# FPGA2_POWER.net
KiCad netlist of a schematic drawn in Altium Designer
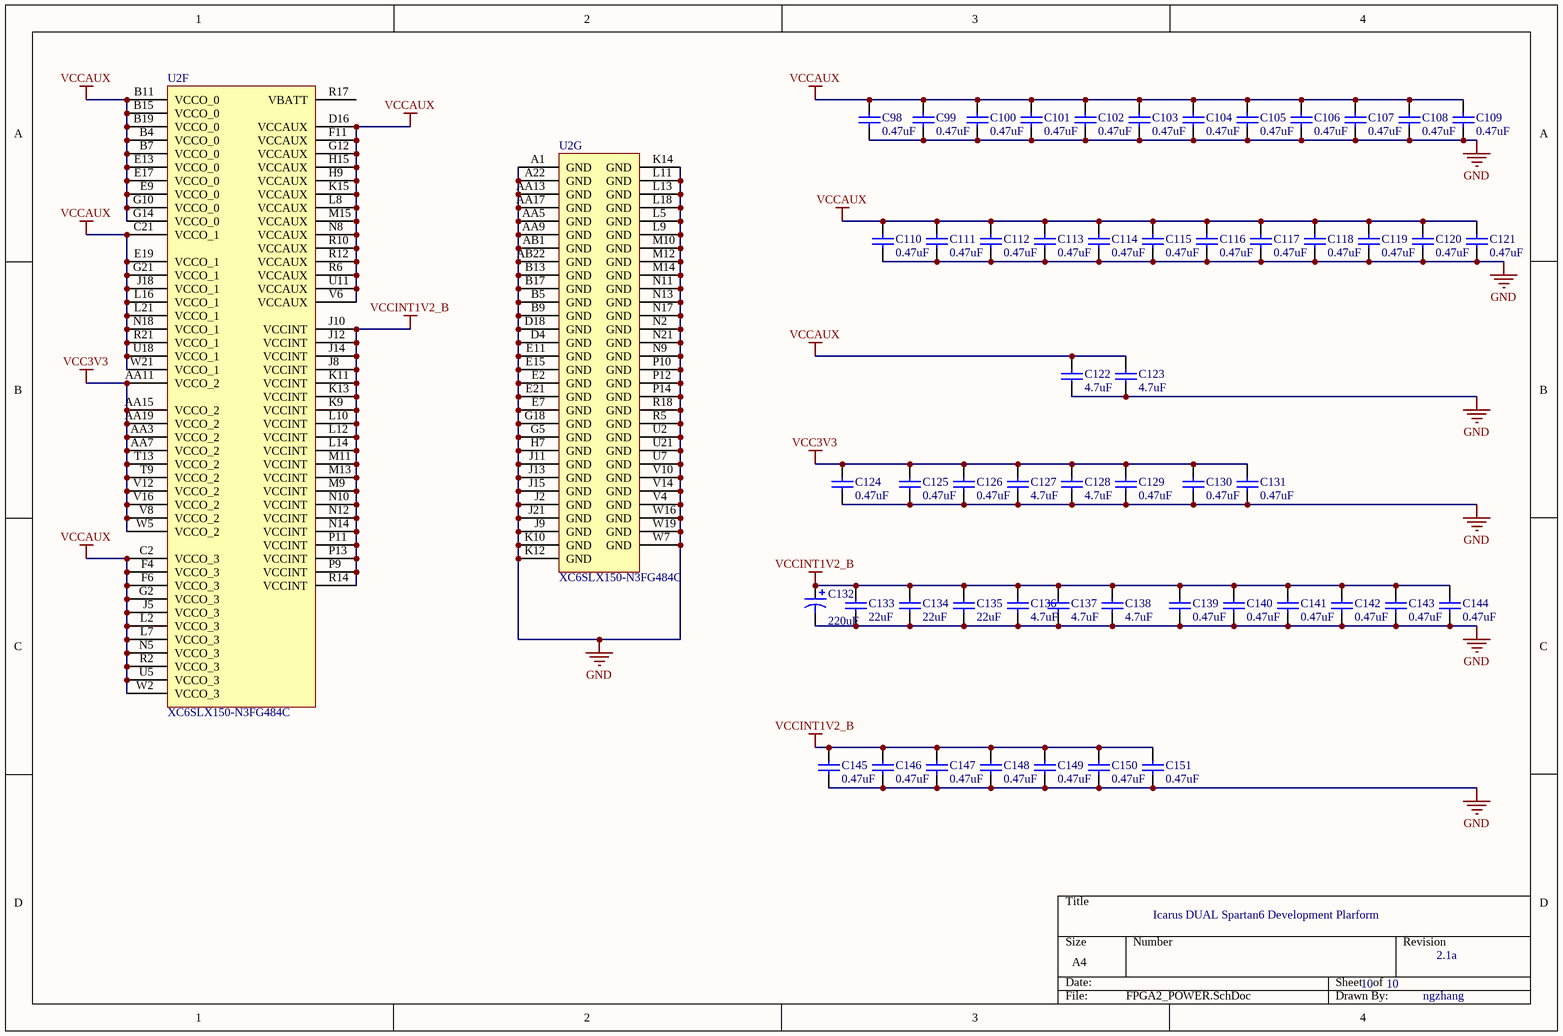
[diagram p0: FPGA2_POWER.SchDoc]

(export (version "E")
  (design (tool "Eeschema 10.0.6"))
  (components
    (comp (ref "C98")
      (value "0.47uF")
      (footprint "0402")
      (description "Capacitor (Semiconductor SIM Model)")
      (fields (field (name "PUBLISHER") "Altium Limited"))
      (libsource (lib "Miscellaneous Devices") (part "Cap Semi"))
    )
    (comp (ref "C99")
      (value "0.47uF")
      (footprint "0402")
      (description "Capacitor (Semiconductor SIM Model)")
      (fields (field (name "PUBLISHER") "Altium Limited"))
      (libsource (lib "Miscellaneous Devices") (part "Cap Semi"))
    )
    (comp (ref "C100")
      (value "0.47uF")
      (footprint "0402")
      (description "Capacitor (Semiconductor SIM Model)")
      (fields (field (name "PUBLISHER") "Altium Limited"))
      (libsource (lib "Miscellaneous Devices") (part "Cap Semi"))
    )
    (comp (ref "C101")
      (value "0.47uF")
      (footprint "0402")
      (description "Capacitor (Semiconductor SIM Model)")
      (fields (field (name "PUBLISHER") "Altium Limited"))
      (libsource (lib "Miscellaneous Devices") (part "Cap Semi"))
    )
    (comp (ref "C102")
      (value "0.47uF")
      (footprint "0402")
      (description "Capacitor (Semiconductor SIM Model)")
      (fields (field (name "PUBLISHER") "Altium Limited"))
      (libsource (lib "Miscellaneous Devices") (part "Cap Semi"))
    )
    (comp (ref "C103")
      (value "0.47uF")
      (footprint "0402")
      (description "Capacitor (Semiconductor SIM Model)")
      (fields (field (name "PUBLISHER") "Altium Limited"))
      (libsource (lib "Miscellaneous Devices") (part "Cap Semi"))
    )
    (comp (ref "C104")
      (value "0.47uF")
      (footprint "0402")
      (description "Capacitor (Semiconductor SIM Model)")
      (fields (field (name "PUBLISHER") "Altium Limited"))
      (libsource (lib "Miscellaneous Devices") (part "Cap Semi"))
    )
    (comp (ref "C105")
      (value "0.47uF")
      (footprint "0402")
      (description "Capacitor (Semiconductor SIM Model)")
      (fields (field (name "PUBLISHER") "Altium Limited"))
      (libsource (lib "Miscellaneous Devices") (part "Cap Semi"))
    )
    (comp (ref "C106")
      (value "0.47uF")
      (footprint "0402")
      (description "Capacitor (Semiconductor SIM Model)")
      (fields (field (name "PUBLISHER") "Altium Limited"))
      (libsource (lib "Miscellaneous Devices") (part "Cap Semi"))
    )
    (comp (ref "C107")
      (value "0.47uF")
      (footprint "0402")
      (description "Capacitor (Semiconductor SIM Model)")
      (fields (field (name "PUBLISHER") "Altium Limited"))
      (libsource (lib "Miscellaneous Devices") (part "Cap Semi"))
    )
    (comp (ref "C108")
      (value "0.47uF")
      (footprint "0402")
      (description "Capacitor (Semiconductor SIM Model)")
      (fields (field (name "PUBLISHER") "Altium Limited"))
      (libsource (lib "Miscellaneous Devices") (part "Cap Semi"))
    )
    (comp (ref "C109")
      (value "0.47uF")
      (footprint "0402")
      (description "Capacitor (Semiconductor SIM Model)")
      (fields (field (name "PUBLISHER") "Altium Limited"))
      (libsource (lib "Miscellaneous Devices") (part "Cap Semi"))
    )
    (comp (ref "C110")
      (value "0.47uF")
      (footprint "0402")
      (description "Capacitor (Semiconductor SIM Model)")
      (fields (field (name "PUBLISHER") "Altium Limited"))
      (libsource (lib "Miscellaneous Devices") (part "Cap Semi"))
    )
    (comp (ref "C111")
      (value "0.47uF")
      (footprint "0402")
      (description "Capacitor (Semiconductor SIM Model)")
      (fields (field (name "PUBLISHER") "Altium Limited"))
      (libsource (lib "Miscellaneous Devices") (part "Cap Semi"))
    )
    (comp (ref "C112")
      (value "0.47uF")
      (footprint "0402")
      (description "Capacitor (Semiconductor SIM Model)")
      (fields (field (name "PUBLISHER") "Altium Limited"))
      (libsource (lib "Miscellaneous Devices") (part "Cap Semi"))
    )
    (comp (ref "C113")
      (value "0.47uF")
      (footprint "0402")
      (description "Capacitor (Semiconductor SIM Model)")
      (fields (field (name "PUBLISHER") "Altium Limited"))
      (libsource (lib "Miscellaneous Devices") (part "Cap Semi"))
    )
    (comp (ref "C114")
      (value "0.47uF")
      (footprint "0402")
      (description "Capacitor (Semiconductor SIM Model)")
      (fields (field (name "PUBLISHER") "Altium Limited"))
      (libsource (lib "Miscellaneous Devices") (part "Cap Semi"))
    )
    (comp (ref "C115")
      (value "0.47uF")
      (footprint "0402")
      (description "Capacitor (Semiconductor SIM Model)")
      (fields (field (name "PUBLISHER") "Altium Limited"))
      (libsource (lib "Miscellaneous Devices") (part "Cap Semi"))
    )
    (comp (ref "C116")
      (value "0.47uF")
      (footprint "0402")
      (description "Capacitor (Semiconductor SIM Model)")
      (fields (field (name "PUBLISHER") "Altium Limited"))
      (libsource (lib "Miscellaneous Devices") (part "Cap Semi"))
    )
    (comp (ref "C117")
      (value "0.47uF")
      (footprint "0402")
      (description "Capacitor (Semiconductor SIM Model)")
      (fields (field (name "PUBLISHER") "Altium Limited"))
      (libsource (lib "Miscellaneous Devices") (part "Cap Semi"))
    )
    (comp (ref "C118")
      (value "0.47uF")
      (footprint "0402")
      (description "Capacitor (Semiconductor SIM Model)")
      (fields (field (name "PUBLISHER") "Altium Limited"))
      (libsource (lib "Miscellaneous Devices") (part "Cap Semi"))
    )
    (comp (ref "C119")
      (value "0.47uF")
      (footprint "0402")
      (description "Capacitor (Semiconductor SIM Model)")
      (fields (field (name "PUBLISHER") "Altium Limited"))
      (libsource (lib "Miscellaneous Devices") (part "Cap Semi"))
    )
    (comp (ref "C120")
      (value "0.47uF")
      (footprint "0402")
      (description "Capacitor (Semiconductor SIM Model)")
      (fields (field (name "PUBLISHER") "Altium Limited"))
      (libsource (lib "Miscellaneous Devices") (part "Cap Semi"))
    )
    (comp (ref "C121")
      (value "0.47uF")
      (footprint "0402")
      (description "Capacitor (Semiconductor SIM Model)")
      (fields (field (name "PUBLISHER") "Altium Limited"))
      (libsource (lib "Miscellaneous Devices") (part "Cap Semi"))
    )
    (comp (ref "C122")
      (value "4.7uF")
      (footprint "C0805")
      (description "Capacitor (Semiconductor SIM Model)")
      (fields (field (name "PUBLISHER") "Altium Limited"))
      (libsource (lib "Miscellaneous Devices") (part "Cap Semi"))
    )
    (comp (ref "C123")
      (value "4.7uF")
      (footprint "C0805")
      (description "Capacitor (Semiconductor SIM Model)")
      (fields (field (name "PUBLISHER") "Altium Limited"))
      (libsource (lib "Miscellaneous Devices") (part "Cap Semi"))
    )
    (comp (ref "C124")
      (value "0.47uF")
      (footprint "0402")
      (description "Capacitor (Semiconductor SIM Model)")
      (fields (field (name "PUBLISHER") "Altium Limited"))
      (libsource (lib "Miscellaneous Devices") (part "Cap Semi"))
    )
    (comp (ref "C125")
      (value "0.47uF")
      (footprint "0402")
      (description "Capacitor (Semiconductor SIM Model)")
      (fields (field (name "PUBLISHER") "Altium Limited"))
      (libsource (lib "Miscellaneous Devices") (part "Cap Semi"))
    )
    (comp (ref "C126")
      (value "0.47uF")
      (footprint "0402")
      (description "Capacitor (Semiconductor SIM Model)")
      (fields (field (name "PUBLISHER") "Altium Limited"))
      (libsource (lib "Miscellaneous Devices") (part "Cap Semi"))
    )
    (comp (ref "C127")
      (value "4.7uF")
      (footprint "C0805")
      (description "Capacitor (Semiconductor SIM Model)")
      (fields (field (name "PUBLISHER") "Altium Limited"))
      (libsource (lib "Miscellaneous Devices") (part "Cap Semi"))
    )
    (comp (ref "C128")
      (value "4.7uF")
      (footprint "C0805")
      (description "Capacitor (Semiconductor SIM Model)")
      (fields (field (name "PUBLISHER") "Altium Limited"))
      (libsource (lib "Miscellaneous Devices") (part "Cap Semi"))
    )
    (comp (ref "C129")
      (value "0.47uF")
      (footprint "0402")
      (description "Capacitor (Semiconductor SIM Model)")
      (fields (field (name "PUBLISHER") "Altium Limited"))
      (libsource (lib "Miscellaneous Devices") (part "Cap Semi"))
    )
    (comp (ref "C130")
      (value "0.47uF")
      (footprint "0402")
      (description "Capacitor (Semiconductor SIM Model)")
      (fields (field (name "PUBLISHER") "Altium Limited"))
      (libsource (lib "Miscellaneous Devices") (part "Cap Semi"))
    )
    (comp (ref "C131")
      (value "0.47uF")
      (footprint "0402")
      (description "Capacitor (Semiconductor SIM Model)")
      (fields (field (name "PUBLISHER") "Altium Limited"))
      (libsource (lib "Miscellaneous Devices") (part "Cap Semi"))
    )
    (comp (ref "C132")
      (value "220uF")
      (footprint "D")
      (description "Polarized Capacitor (Surface Mount)")
      (fields (field (name "PUBLISHER") "Altium Limited"))
      (libsource (lib "Miscellaneous Devices") (part "Cap Pol3"))
    )
    (comp (ref "C133")
      (value "22uF")
      (footprint "C1206")
      (description "Capacitor (Semiconductor SIM Model)")
      (fields (field (name "PUBLISHER") "Altium Limited"))
      (libsource (lib "Miscellaneous Devices") (part "Cap Semi"))
    )
    (comp (ref "C134")
      (value "22uF")
      (footprint "C1206")
      (description "Capacitor (Semiconductor SIM Model)")
      (fields (field (name "PUBLISHER") "Altium Limited"))
      (libsource (lib "Miscellaneous Devices") (part "Cap Semi"))
    )
    (comp (ref "C135")
      (value "22uF")
      (footprint "C1206")
      (description "Capacitor (Semiconductor SIM Model)")
      (fields (field (name "PUBLISHER") "Altium Limited"))
      (libsource (lib "Miscellaneous Devices") (part "Cap Semi"))
    )
    (comp (ref "C136")
      (value "4.7uF")
      (footprint "C0805")
      (description "Capacitor (Semiconductor SIM Model)")
      (fields (field (name "PUBLISHER") "Altium Limited"))
      (libsource (lib "Miscellaneous Devices") (part "Cap Semi"))
    )
    (comp (ref "C137")
      (value "4.7uF")
      (footprint "C0805")
      (description "Capacitor (Semiconductor SIM Model)")
      (fields (field (name "PUBLISHER") "Altium Limited"))
      (libsource (lib "Miscellaneous Devices") (part "Cap Semi"))
    )
    (comp (ref "C138")
      (value "4.7uF")
      (footprint "C0805")
      (description "Capacitor (Semiconductor SIM Model)")
      (fields (field (name "PUBLISHER") "Altium Limited"))
      (libsource (lib "Miscellaneous Devices") (part "Cap Semi"))
    )
    (comp (ref "C139")
      (value "0.47uF")
      (footprint "0402")
      (description "Capacitor (Semiconductor SIM Model)")
      (fields (field (name "PUBLISHER") "Altium Limited"))
      (libsource (lib "Miscellaneous Devices") (part "Cap Semi"))
    )
    (comp (ref "C140")
      (value "0.47uF")
      (footprint "0402")
      (description "Capacitor (Semiconductor SIM Model)")
      (fields (field (name "PUBLISHER") "Altium Limited"))
      (libsource (lib "Miscellaneous Devices") (part "Cap Semi"))
    )
    (comp (ref "C141")
      (value "0.47uF")
      (footprint "0402")
      (description "Capacitor (Semiconductor SIM Model)")
      (fields (field (name "PUBLISHER") "Altium Limited"))
      (libsource (lib "Miscellaneous Devices") (part "Cap Semi"))
    )
    (comp (ref "C142")
      (value "0.47uF")
      (footprint "0402")
      (description "Capacitor (Semiconductor SIM Model)")
      (fields (field (name "PUBLISHER") "Altium Limited"))
      (libsource (lib "Miscellaneous Devices") (part "Cap Semi"))
    )
    (comp (ref "C143")
      (value "0.47uF")
      (footprint "0402")
      (description "Capacitor (Semiconductor SIM Model)")
      (fields (field (name "PUBLISHER") "Altium Limited"))
      (libsource (lib "Miscellaneous Devices") (part "Cap Semi"))
    )
    (comp (ref "C144")
      (value "0.47uF")
      (footprint "0402")
      (description "Capacitor (Semiconductor SIM Model)")
      (fields (field (name "PUBLISHER") "Altium Limited"))
      (libsource (lib "Miscellaneous Devices") (part "Cap Semi"))
    )
    (comp (ref "C145")
      (value "0.47uF")
      (footprint "0402")
      (description "Capacitor (Semiconductor SIM Model)")
      (fields (field (name "PUBLISHER") "Altium Limited"))
      (libsource (lib "Miscellaneous Devices") (part "Cap Semi"))
    )
    (comp (ref "C146")
      (value "0.47uF")
      (footprint "0402")
      (description "Capacitor (Semiconductor SIM Model)")
      (fields (field (name "PUBLISHER") "Altium Limited"))
      (libsource (lib "Miscellaneous Devices") (part "Cap Semi"))
    )
    (comp (ref "C147")
      (value "0.47uF")
      (footprint "0402")
      (description "Capacitor (Semiconductor SIM Model)")
      (fields (field (name "PUBLISHER") "Altium Limited"))
      (libsource (lib "Miscellaneous Devices") (part "Cap Semi"))
    )
    (comp (ref "C148")
      (value "0.47uF")
      (footprint "0402")
      (description "Capacitor (Semiconductor SIM Model)")
      (fields (field (name "PUBLISHER") "Altium Limited"))
      (libsource (lib "Miscellaneous Devices") (part "Cap Semi"))
    )
    (comp (ref "C149")
      (value "0.47uF")
      (footprint "0402")
      (description "Capacitor (Semiconductor SIM Model)")
      (fields (field (name "PUBLISHER") "Altium Limited"))
      (libsource (lib "Miscellaneous Devices") (part "Cap Semi"))
    )
    (comp (ref "C150")
      (value "0.47uF")
      (footprint "0402")
      (description "Capacitor (Semiconductor SIM Model)")
      (fields (field (name "PUBLISHER") "Altium Limited"))
      (libsource (lib "Miscellaneous Devices") (part "Cap Semi"))
    )
    (comp (ref "C151")
      (value "0.47uF")
      (footprint "0402")
      (description "Capacitor (Semiconductor SIM Model)")
      (fields (field (name "PUBLISHER") "Altium Limited"))
      (libsource (lib "Miscellaneous Devices") (part "Cap Semi"))
    )
    (comp (ref "U2")
      (value "XC6SLX150-N3FG484C")
      (footprint "FG484")
      (fields (field (name "PUBLISHER") "Altium Limited"))
      (libsource (lib "Xilinx Spartan-6") (part "XC6SLX150-N3FG484C"))
    )
  )
  (nets
    (net (code "1") (name "GND") (class "Default")
      (node (ref "C100") (pin "1") (pinfunction "1_1") (pintype "passive"))
      (node (ref "C101") (pin "1") (pinfunction "1_1") (pintype "passive"))
      (node (ref "C102") (pin "1") (pinfunction "1_1") (pintype "passive"))
      (node (ref "C103") (pin "1") (pinfunction "1_1") (pintype "passive"))
      (node (ref "C104") (pin "1") (pinfunction "1_1") (pintype "passive"))
      (node (ref "C105") (pin "1") (pinfunction "1_1") (pintype "passive"))
      (node (ref "C106") (pin "1") (pinfunction "1_1") (pintype "passive"))
      (node (ref "C107") (pin "1") (pinfunction "1_1") (pintype "passive"))
      (node (ref "C108") (pin "1") (pinfunction "1_1") (pintype "passive"))
      (node (ref "C109") (pin "1") (pinfunction "1_1") (pintype "passive"))
      (node (ref "C110") (pin "1") (pinfunction "1_1") (pintype "passive"))
      (node (ref "C111") (pin "1") (pinfunction "1_1") (pintype "passive"))
      (node (ref "C112") (pin "1") (pinfunction "1_1") (pintype "passive"))
      (node (ref "C113") (pin "1") (pinfunction "1_1") (pintype "passive"))
      (node (ref "C114") (pin "1") (pinfunction "1_1") (pintype "passive"))
      (node (ref "C115") (pin "1") (pinfunction "1_1") (pintype "passive"))
      (node (ref "C116") (pin "1") (pinfunction "1_1") (pintype "passive"))
      (node (ref "C117") (pin "1") (pinfunction "1_1") (pintype "passive"))
      (node (ref "C118") (pin "1") (pinfunction "1_1") (pintype "passive"))
      (node (ref "C119") (pin "1") (pinfunction "1_1") (pintype "passive"))
      (node (ref "C120") (pin "1") (pinfunction "1_1") (pintype "passive"))
      (node (ref "C121") (pin "1") (pinfunction "1_1") (pintype "passive"))
      (node (ref "C122") (pin "1") (pinfunction "1_1") (pintype "passive"))
      (node (ref "C123") (pin "1") (pinfunction "1_1") (pintype "passive"))
      (node (ref "C124") (pin "1") (pinfunction "1_1") (pintype "passive"))
      (node (ref "C125") (pin "1") (pinfunction "1_1") (pintype "passive"))
      (node (ref "C126") (pin "1") (pinfunction "1_1") (pintype "passive"))
      (node (ref "C127") (pin "1") (pinfunction "1_1") (pintype "passive"))
      (node (ref "C128") (pin "1") (pinfunction "1_1") (pintype "passive"))
      (node (ref "C129") (pin "1") (pinfunction "1_1") (pintype "passive"))
      (node (ref "C130") (pin "1") (pinfunction "1_1") (pintype "passive"))
      (node (ref "C131") (pin "1") (pinfunction "1_1") (pintype "passive"))
      (node (ref "C132") (pin "2") (pinfunction "2_2") (pintype "passive"))
      (node (ref "C133") (pin "1") (pinfunction "1_1") (pintype "passive"))
      (node (ref "C134") (pin "1") (pinfunction "1_1") (pintype "passive"))
      (node (ref "C135") (pin "1") (pinfunction "1_1") (pintype "passive"))
      (node (ref "C136") (pin "1") (pinfunction "1_1") (pintype "passive"))
      (node (ref "C137") (pin "1") (pinfunction "1_1") (pintype "passive"))
      (node (ref "C138") (pin "1") (pinfunction "1_1") (pintype "passive"))
      (node (ref "C139") (pin "1") (pinfunction "1_1") (pintype "passive"))
      (node (ref "C140") (pin "1") (pinfunction "1_1") (pintype "passive"))
      (node (ref "C141") (pin "1") (pinfunction "1_1") (pintype "passive"))
      (node (ref "C142") (pin "1") (pinfunction "1_1") (pintype "passive"))
      (node (ref "C143") (pin "1") (pinfunction "1_1") (pintype "passive"))
      (node (ref "C144") (pin "1") (pinfunction "1_1") (pintype "passive"))
      (node (ref "C145") (pin "1") (pinfunction "1_1") (pintype "passive"))
      (node (ref "C146") (pin "1") (pinfunction "1_1") (pintype "passive"))
      (node (ref "C147") (pin "1") (pinfunction "1_1") (pintype "passive"))
      (node (ref "C148") (pin "1") (pinfunction "1_1") (pintype "passive"))
      (node (ref "C149") (pin "1") (pinfunction "1_1") (pintype "passive"))
      (node (ref "C150") (pin "1") (pinfunction "1_1") (pintype "passive"))
      (node (ref "C151") (pin "1") (pinfunction "1_1") (pintype "passive"))
      (node (ref "C98") (pin "1") (pinfunction "1_1") (pintype "passive"))
      (node (ref "C99") (pin "1") (pinfunction "1_1") (pintype "passive"))
      (node (ref "U2") (pin "A1") (pinfunction "GND_A1") (pintype "power_in"))
      (node (ref "U2") (pin "A22") (pinfunction "GND_A22") (pintype "power_in"))
      (node (ref "U2") (pin "AA13") (pinfunction "GND_AA13") (pintype "power_in"))
      (node (ref "U2") (pin "AA17") (pinfunction "GND_AA17") (pintype "power_in"))
      (node (ref "U2") (pin "AA5") (pinfunction "GND_AA5") (pintype "power_in"))
      (node (ref "U2") (pin "AA9") (pinfunction "GND_AA9") (pintype "power_in"))
      (node (ref "U2") (pin "AB1") (pinfunction "GND_AB1") (pintype "power_in"))
      (node (ref "U2") (pin "AB22") (pinfunction "GND_AB22") (pintype "power_in"))
      (node (ref "U2") (pin "B13") (pinfunction "GND_B13") (pintype "power_in"))
      (node (ref "U2") (pin "B17") (pinfunction "GND_B17") (pintype "power_in"))
      (node (ref "U2") (pin "B5") (pinfunction "GND_B5") (pintype "power_in"))
      (node (ref "U2") (pin "B9") (pinfunction "GND_B9") (pintype "power_in"))
      (node (ref "U2") (pin "D18") (pinfunction "GND_D18") (pintype "power_in"))
      (node (ref "U2") (pin "D4") (pinfunction "GND_D4") (pintype "power_in"))
      (node (ref "U2") (pin "E11") (pinfunction "GND_E11") (pintype "power_in"))
      (node (ref "U2") (pin "E15") (pinfunction "GND_E15") (pintype "power_in"))
      (node (ref "U2") (pin "E2") (pinfunction "GND_E2") (pintype "power_in"))
      (node (ref "U2") (pin "E21") (pinfunction "GND_E21") (pintype "power_in"))
      (node (ref "U2") (pin "E7") (pinfunction "GND_E7") (pintype "power_in"))
      (node (ref "U2") (pin "G18") (pinfunction "GND_G18") (pintype "power_in"))
      (node (ref "U2") (pin "G5") (pinfunction "GND_G5") (pintype "power_in"))
      (node (ref "U2") (pin "H7") (pinfunction "GND_H7") (pintype "power_in"))
      (node (ref "U2") (pin "J11") (pinfunction "GND_J11") (pintype "power_in"))
      (node (ref "U2") (pin "J13") (pinfunction "GND_J13") (pintype "power_in"))
      (node (ref "U2") (pin "J15") (pinfunction "GND_J15") (pintype "power_in"))
      (node (ref "U2") (pin "J2") (pinfunction "GND_J2") (pintype "power_in"))
      (node (ref "U2") (pin "J21") (pinfunction "GND_J21") (pintype "power_in"))
      (node (ref "U2") (pin "J9") (pinfunction "GND_J9") (pintype "power_in"))
      (node (ref "U2") (pin "K10") (pinfunction "GND_K10") (pintype "power_in"))
      (node (ref "U2") (pin "K12") (pinfunction "GND_K12") (pintype "power_in"))
      (node (ref "U2") (pin "K14") (pinfunction "GND_K14") (pintype "power_in"))
      (node (ref "U2") (pin "L11") (pinfunction "GND_L11") (pintype "power_in"))
      (node (ref "U2") (pin "L13") (pinfunction "GND_L13") (pintype "power_in"))
      (node (ref "U2") (pin "L18") (pinfunction "GND_L18") (pintype "power_in"))
      (node (ref "U2") (pin "L5") (pinfunction "GND_L5") (pintype "power_in"))
      (node (ref "U2") (pin "L9") (pinfunction "GND_L9") (pintype "power_in"))
      (node (ref "U2") (pin "M10") (pinfunction "GND_M10") (pintype "power_in"))
      (node (ref "U2") (pin "M12") (pinfunction "GND_M12") (pintype "power_in"))
      (node (ref "U2") (pin "M14") (pinfunction "GND_M14") (pintype "power_in"))
      (node (ref "U2") (pin "N11") (pinfunction "GND_N11") (pintype "power_in"))
      (node (ref "U2") (pin "N13") (pinfunction "GND_N13") (pintype "power_in"))
      (node (ref "U2") (pin "N17") (pinfunction "GND_N17") (pintype "power_in"))
      (node (ref "U2") (pin "N2") (pinfunction "GND_N2") (pintype "power_in"))
      (node (ref "U2") (pin "N21") (pinfunction "GND_N21") (pintype "power_in"))
      (node (ref "U2") (pin "N9") (pinfunction "GND_N9") (pintype "power_in"))
      (node (ref "U2") (pin "P10") (pinfunction "GND_P10") (pintype "power_in"))
      (node (ref "U2") (pin "P12") (pinfunction "GND_P12") (pintype "power_in"))
      (node (ref "U2") (pin "P14") (pinfunction "GND_P14") (pintype "power_in"))
      (node (ref "U2") (pin "R18") (pinfunction "GND_R18") (pintype "power_in"))
      (node (ref "U2") (pin "R5") (pinfunction "GND_R5") (pintype "power_in"))
      (node (ref "U2") (pin "U2") (pinfunction "GND_U2") (pintype "power_in"))
      (node (ref "U2") (pin "U21") (pinfunction "GND_U21") (pintype "power_in"))
      (node (ref "U2") (pin "U7") (pinfunction "GND_U7") (pintype "power_in"))
      (node (ref "U2") (pin "V10") (pinfunction "GND_V10") (pintype "power_in"))
      (node (ref "U2") (pin "V14") (pinfunction "GND_V14") (pintype "power_in"))
      (node (ref "U2") (pin "V4") (pinfunction "GND_V4") (pintype "power_in"))
      (node (ref "U2") (pin "W16") (pinfunction "GND_W16") (pintype "power_in"))
      (node (ref "U2") (pin "W19") (pinfunction "GND_W19") (pintype "power_in"))
      (node (ref "U2") (pin "W7") (pinfunction "GND_W7") (pintype "power_in"))
    )
    (net (code "2") (name "VCC3V3") (class "Default")
      (node (ref "C124") (pin "2") (pinfunction "2_2") (pintype "passive"))
      (node (ref "C125") (pin "2") (pinfunction "2_2") (pintype "passive"))
      (node (ref "C126") (pin "2") (pinfunction "2_2") (pintype "passive"))
      (node (ref "C127") (pin "2") (pinfunction "2_2") (pintype "passive"))
      (node (ref "C128") (pin "2") (pinfunction "2_2") (pintype "passive"))
      (node (ref "C129") (pin "2") (pinfunction "2_2") (pintype "passive"))
      (node (ref "C130") (pin "2") (pinfunction "2_2") (pintype "passive"))
      (node (ref "C131") (pin "2") (pinfunction "2_2") (pintype "passive"))
      (node (ref "U2") (pin "AA11") (pinfunction "VCCO_2_AA11") (pintype "power_in"))
      (node (ref "U2") (pin "AA15") (pinfunction "VCCO_2_AA15") (pintype "power_in"))
      (node (ref "U2") (pin "AA19") (pinfunction "VCCO_2_AA19") (pintype "power_in"))
      (node (ref "U2") (pin "AA3") (pinfunction "VCCO_2_AA3") (pintype "power_in"))
      (node (ref "U2") (pin "AA7") (pinfunction "VCCO_2_AA7") (pintype "power_in"))
      (node (ref "U2") (pin "T13") (pinfunction "VCCO_2_T13") (pintype "power_in"))
      (node (ref "U2") (pin "T9") (pinfunction "VCCO_2_T9") (pintype "power_in"))
      (node (ref "U2") (pin "V12") (pinfunction "VCCO_2_V12") (pintype "power_in"))
      (node (ref "U2") (pin "V16") (pinfunction "VCCO_2_V16") (pintype "power_in"))
      (node (ref "U2") (pin "V8") (pinfunction "VCCO_2_V8") (pintype "power_in"))
      (node (ref "U2") (pin "W5") (pinfunction "VCCO_2_W5") (pintype "power_in"))
    )
    (net (code "3") (name "VCCAUX") (class "Default")
      (node (ref "C100") (pin "2") (pinfunction "2_2") (pintype "passive"))
      (node (ref "C101") (pin "2") (pinfunction "2_2") (pintype "passive"))
      (node (ref "C102") (pin "2") (pinfunction "2_2") (pintype "passive"))
      (node (ref "C103") (pin "2") (pinfunction "2_2") (pintype "passive"))
      (node (ref "C104") (pin "2") (pinfunction "2_2") (pintype "passive"))
      (node (ref "C105") (pin "2") (pinfunction "2_2") (pintype "passive"))
      (node (ref "C106") (pin "2") (pinfunction "2_2") (pintype "passive"))
      (node (ref "C107") (pin "2") (pinfunction "2_2") (pintype "passive"))
      (node (ref "C108") (pin "2") (pinfunction "2_2") (pintype "passive"))
      (node (ref "C109") (pin "2") (pinfunction "2_2") (pintype "passive"))
      (node (ref "C110") (pin "2") (pinfunction "2_2") (pintype "passive"))
      (node (ref "C111") (pin "2") (pinfunction "2_2") (pintype "passive"))
      (node (ref "C112") (pin "2") (pinfunction "2_2") (pintype "passive"))
      (node (ref "C113") (pin "2") (pinfunction "2_2") (pintype "passive"))
      (node (ref "C114") (pin "2") (pinfunction "2_2") (pintype "passive"))
      (node (ref "C115") (pin "2") (pinfunction "2_2") (pintype "passive"))
      (node (ref "C116") (pin "2") (pinfunction "2_2") (pintype "passive"))
      (node (ref "C117") (pin "2") (pinfunction "2_2") (pintype "passive"))
      (node (ref "C118") (pin "2") (pinfunction "2_2") (pintype "passive"))
      (node (ref "C119") (pin "2") (pinfunction "2_2") (pintype "passive"))
      (node (ref "C120") (pin "2") (pinfunction "2_2") (pintype "passive"))
      (node (ref "C121") (pin "2") (pinfunction "2_2") (pintype "passive"))
      (node (ref "C122") (pin "2") (pinfunction "2_2") (pintype "passive"))
      (node (ref "C123") (pin "2") (pinfunction "2_2") (pintype "passive"))
      (node (ref "C98") (pin "2") (pinfunction "2_2") (pintype "passive"))
      (node (ref "C99") (pin "2") (pinfunction "2_2") (pintype "passive"))
      (node (ref "U2") (pin "B11") (pinfunction "VCCO_0_B11") (pintype "power_in"))
      (node (ref "U2") (pin "B15") (pinfunction "VCCO_0_B15") (pintype "power_in"))
      (node (ref "U2") (pin "B19") (pinfunction "VCCO_0_B19") (pintype "power_in"))
      (node (ref "U2") (pin "B4") (pinfunction "VCCO_0_B4") (pintype "power_in"))
      (node (ref "U2") (pin "B7") (pinfunction "VCCO_0_B7") (pintype "power_in"))
      (node (ref "U2") (pin "C2") (pinfunction "VCCO_3_C2") (pintype "power_in"))
      (node (ref "U2") (pin "C21") (pinfunction "VCCO_1_C21") (pintype "power_in"))
      (node (ref "U2") (pin "D16") (pinfunction "VCCAUX_D16") (pintype "power_in"))
      (node (ref "U2") (pin "E13") (pinfunction "VCCO_0_E13") (pintype "power_in"))
      (node (ref "U2") (pin "E17") (pinfunction "VCCO_0_E17") (pintype "power_in"))
      (node (ref "U2") (pin "E19") (pinfunction "VCCO_1_E19") (pintype "power_in"))
      (node (ref "U2") (pin "E9") (pinfunction "VCCO_0_E9") (pintype "power_in"))
      (node (ref "U2") (pin "F11") (pinfunction "VCCAUX_F11") (pintype "power_in"))
      (node (ref "U2") (pin "F4") (pinfunction "VCCO_3_F4") (pintype "power_in"))
      (node (ref "U2") (pin "F6") (pinfunction "VCCO_3_F6") (pintype "power_in"))
      (node (ref "U2") (pin "G10") (pinfunction "VCCO_0_G10") (pintype "power_in"))
      (node (ref "U2") (pin "G12") (pinfunction "VCCAUX_G12") (pintype "power_in"))
      (node (ref "U2") (pin "G14") (pinfunction "VCCO_0_G14") (pintype "power_in"))
      (node (ref "U2") (pin "G2") (pinfunction "VCCO_3_G2") (pintype "power_in"))
      (node (ref "U2") (pin "G21") (pinfunction "VCCO_1_G21") (pintype "power_in"))
      (node (ref "U2") (pin "H15") (pinfunction "VCCAUX_H15") (pintype "power_in"))
      (node (ref "U2") (pin "H9") (pinfunction "VCCAUX_H9") (pintype "power_in"))
      (node (ref "U2") (pin "J18") (pinfunction "VCCO_1_J18") (pintype "power_in"))
      (node (ref "U2") (pin "J5") (pinfunction "VCCO_3_J5") (pintype "power_in"))
      (node (ref "U2") (pin "K15") (pinfunction "VCCAUX_K15") (pintype "power_in"))
      (node (ref "U2") (pin "L16") (pinfunction "VCCO_1_L16") (pintype "power_in"))
      (node (ref "U2") (pin "L2") (pinfunction "VCCO_3_L2") (pintype "power_in"))
      (node (ref "U2") (pin "L21") (pinfunction "VCCO_1_L21") (pintype "power_in"))
      (node (ref "U2") (pin "L7") (pinfunction "VCCO_3_L7") (pintype "power_in"))
      (node (ref "U2") (pin "L8") (pinfunction "VCCAUX_L8") (pintype "power_in"))
      (node (ref "U2") (pin "M15") (pinfunction "VCCAUX_M15") (pintype "power_in"))
      (node (ref "U2") (pin "N18") (pinfunction "VCCO_1_N18") (pintype "power_in"))
      (node (ref "U2") (pin "N5") (pinfunction "VCCO_3_N5") (pintype "power_in"))
      (node (ref "U2") (pin "N8") (pinfunction "VCCAUX_N8") (pintype "power_in"))
      (node (ref "U2") (pin "R10") (pinfunction "VCCAUX_R10") (pintype "power_in"))
      (node (ref "U2") (pin "R12") (pinfunction "VCCAUX_R12") (pintype "power_in"))
      (node (ref "U2") (pin "R2") (pinfunction "VCCO_3_R2") (pintype "power_in"))
      (node (ref "U2") (pin "R21") (pinfunction "VCCO_1_R21") (pintype "power_in"))
      (node (ref "U2") (pin "R6") (pinfunction "VCCAUX_R6") (pintype "power_in"))
      (node (ref "U2") (pin "U11") (pinfunction "VCCAUX_U11") (pintype "power_in"))
      (node (ref "U2") (pin "U18") (pinfunction "VCCO_1_U18") (pintype "power_in"))
      (node (ref "U2") (pin "U5") (pinfunction "VCCO_3_U5") (pintype "power_in"))
      (node (ref "U2") (pin "V6") (pinfunction "VCCAUX_V6") (pintype "power_in"))
      (node (ref "U2") (pin "W2") (pinfunction "VCCO_3_W2") (pintype "power_in"))
      (node (ref "U2") (pin "W21") (pinfunction "VCCO_1_W21") (pintype "power_in"))
    )
    (net (code "4") (name "VCCINT1V2_B") (class "Default")
      (node (ref "C132") (pin "1") (pinfunction "1_1") (pintype "passive"))
      (node (ref "C133") (pin "2") (pinfunction "2_2") (pintype "passive"))
      (node (ref "C134") (pin "2") (pinfunction "2_2") (pintype "passive"))
      (node (ref "C135") (pin "2") (pinfunction "2_2") (pintype "passive"))
      (node (ref "C136") (pin "2") (pinfunction "2_2") (pintype "passive"))
      (node (ref "C137") (pin "2") (pinfunction "2_2") (pintype "passive"))
      (node (ref "C138") (pin "2") (pinfunction "2_2") (pintype "passive"))
      (node (ref "C139") (pin "2") (pinfunction "2_2") (pintype "passive"))
      (node (ref "C140") (pin "2") (pinfunction "2_2") (pintype "passive"))
      (node (ref "C141") (pin "2") (pinfunction "2_2") (pintype "passive"))
      (node (ref "C142") (pin "2") (pinfunction "2_2") (pintype "passive"))
      (node (ref "C143") (pin "2") (pinfunction "2_2") (pintype "passive"))
      (node (ref "C144") (pin "2") (pinfunction "2_2") (pintype "passive"))
      (node (ref "C145") (pin "2") (pinfunction "2_2") (pintype "passive"))
      (node (ref "C146") (pin "2") (pinfunction "2_2") (pintype "passive"))
      (node (ref "C147") (pin "2") (pinfunction "2_2") (pintype "passive"))
      (node (ref "C148") (pin "2") (pinfunction "2_2") (pintype "passive"))
      (node (ref "C149") (pin "2") (pinfunction "2_2") (pintype "passive"))
      (node (ref "C150") (pin "2") (pinfunction "2_2") (pintype "passive"))
      (node (ref "C151") (pin "2") (pinfunction "2_2") (pintype "passive"))
      (node (ref "U2") (pin "J10") (pinfunction "VCCINT_J10") (pintype "power_in"))
      (node (ref "U2") (pin "J12") (pinfunction "VCCINT_J12") (pintype "power_in"))
      (node (ref "U2") (pin "J14") (pinfunction "VCCINT_J14") (pintype "power_in"))
      (node (ref "U2") (pin "J8") (pinfunction "VCCINT_J8") (pintype "power_in"))
      (node (ref "U2") (pin "K11") (pinfunction "VCCINT_K11") (pintype "power_in"))
      (node (ref "U2") (pin "K13") (pinfunction "VCCINT_K13") (pintype "power_in"))
      (node (ref "U2") (pin "K9") (pinfunction "VCCINT_K9") (pintype "power_in"))
      (node (ref "U2") (pin "L10") (pinfunction "VCCINT_L10") (pintype "power_in"))
      (node (ref "U2") (pin "L12") (pinfunction "VCCINT_L12") (pintype "power_in"))
      (node (ref "U2") (pin "L14") (pinfunction "VCCINT_L14") (pintype "power_in"))
      (node (ref "U2") (pin "M11") (pinfunction "VCCINT_M11") (pintype "power_in"))
      (node (ref "U2") (pin "M13") (pinfunction "VCCINT_M13") (pintype "power_in"))
      (node (ref "U2") (pin "M9") (pinfunction "VCCINT_M9") (pintype "power_in"))
      (node (ref "U2") (pin "N10") (pinfunction "VCCINT_N10") (pintype "power_in"))
      (node (ref "U2") (pin "N12") (pinfunction "VCCINT_N12") (pintype "power_in"))
      (node (ref "U2") (pin "N14") (pinfunction "VCCINT_N14") (pintype "power_in"))
      (node (ref "U2") (pin "P11") (pinfunction "VCCINT_P11") (pintype "power_in"))
      (node (ref "U2") (pin "P13") (pinfunction "VCCINT_P13") (pintype "power_in"))
      (node (ref "U2") (pin "P9") (pinfunction "VCCINT_P9") (pintype "power_in"))
      (node (ref "U2") (pin "R14") (pinfunction "VCCINT_R14") (pintype "power_in"))
    )
    (net (code "5") (name "unconnected-(U2F-VBATT-PadR17)") (class "Default")
      (node (ref "U2") (pin "R17") (pinfunction "VBATT_R17") (pintype "power_in"))
    )
  )
)
